# led_2835_driver_circle_34X34cm.net
KiCad netlist of a schematic drawn in Altium Designer
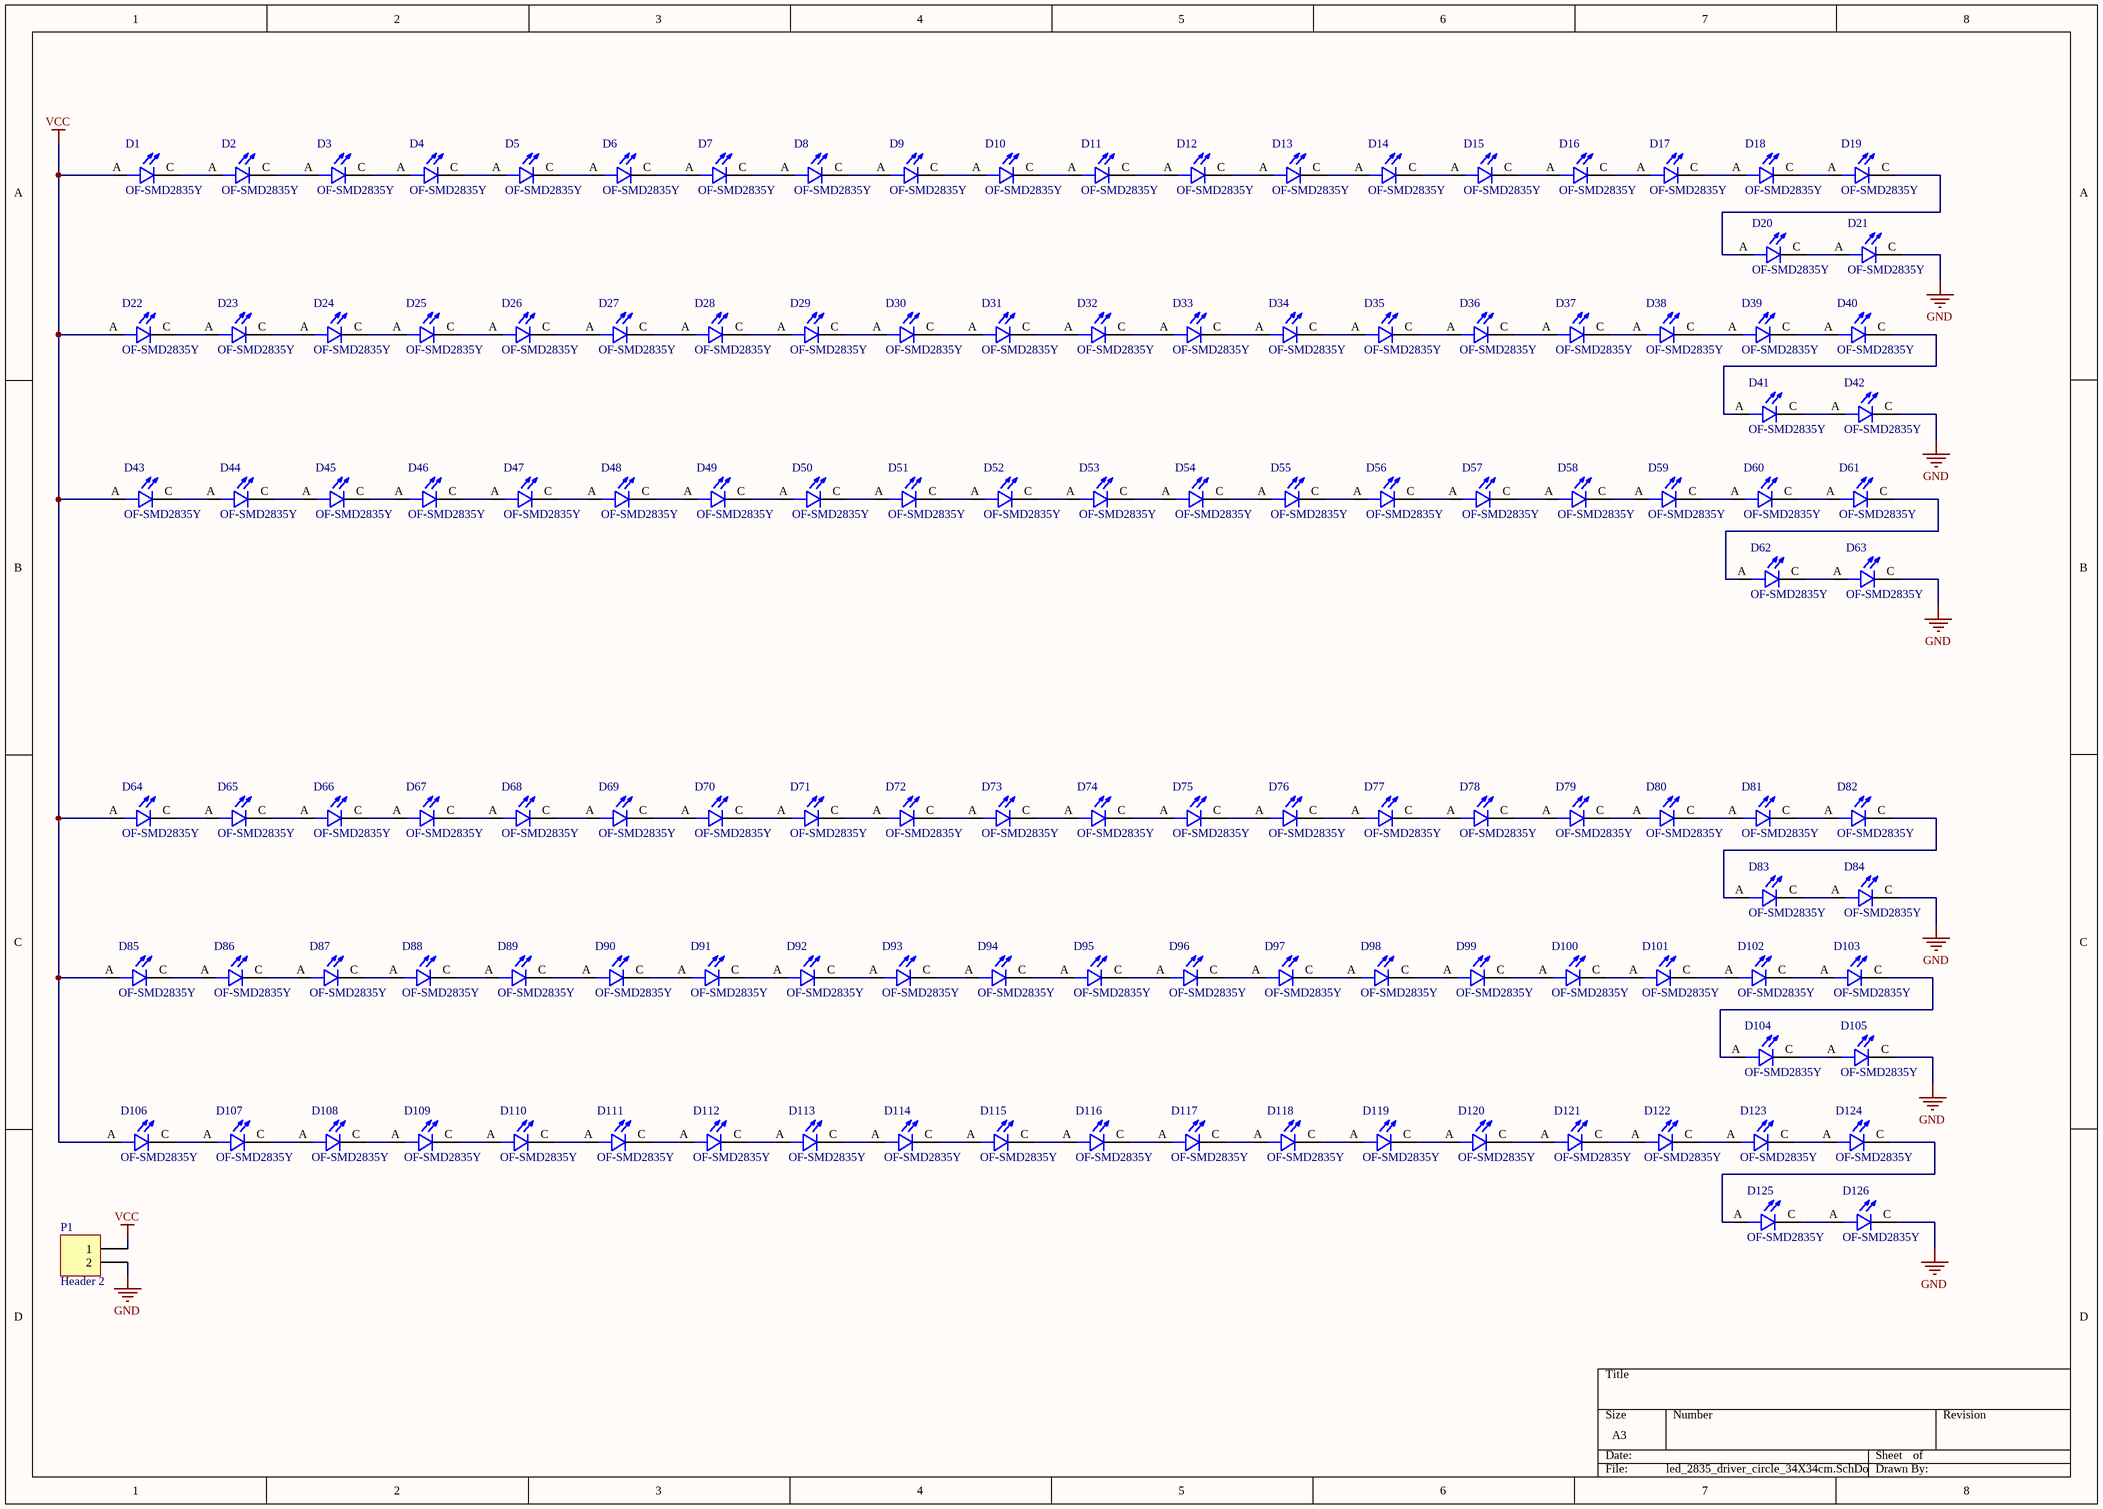
[diagram p0: led_2835_driver_circle_34X34cm.SchDoc]

(export (version "E")
  (design (tool "Eeschema 10.0.6"))
  (components
    (comp (ref "D1")
      (value "OF-SMD2835Y")
      (footprint "LED_OF-SMD2835Y")
      (description "LED; SMD; 2835, PLCC2; yellow; 2200-2800mcd; 2.8x3.5x0.75mm; 120Â°")
      (libsource (lib "OF-SMD2835Y") (part "OF-SMD2835Y"))
    )
    (comp (ref "D2")
      (value "OF-SMD2835Y")
      (footprint "LED_OF-SMD2835Y")
      (description "LED; SMD; 2835, PLCC2; yellow; 2200-2800mcd; 2.8x3.5x0.75mm; 120Â°")
      (libsource (lib "OF-SMD2835Y") (part "OF-SMD2835Y"))
    )
    (comp (ref "D3")
      (value "OF-SMD2835Y")
      (footprint "LED_OF-SMD2835Y")
      (description "LED; SMD; 2835, PLCC2; yellow; 2200-2800mcd; 2.8x3.5x0.75mm; 120Â°")
      (libsource (lib "OF-SMD2835Y") (part "OF-SMD2835Y"))
    )
    (comp (ref "D4")
      (value "OF-SMD2835Y")
      (footprint "LED_OF-SMD2835Y")
      (description "LED; SMD; 2835, PLCC2; yellow; 2200-2800mcd; 2.8x3.5x0.75mm; 120Â°")
      (libsource (lib "OF-SMD2835Y") (part "OF-SMD2835Y"))
    )
    (comp (ref "D5")
      (value "OF-SMD2835Y")
      (footprint "LED_OF-SMD2835Y")
      (description "LED; SMD; 2835, PLCC2; yellow; 2200-2800mcd; 2.8x3.5x0.75mm; 120Â°")
      (libsource (lib "OF-SMD2835Y") (part "OF-SMD2835Y"))
    )
    (comp (ref "D6")
      (value "OF-SMD2835Y")
      (footprint "LED_OF-SMD2835Y")
      (description "LED; SMD; 2835, PLCC2; yellow; 2200-2800mcd; 2.8x3.5x0.75mm; 120Â°")
      (libsource (lib "OF-SMD2835Y") (part "OF-SMD2835Y"))
    )
    (comp (ref "D7")
      (value "OF-SMD2835Y")
      (footprint "LED_OF-SMD2835Y")
      (description "LED; SMD; 2835, PLCC2; yellow; 2200-2800mcd; 2.8x3.5x0.75mm; 120Â°")
      (libsource (lib "OF-SMD2835Y") (part "OF-SMD2835Y"))
    )
    (comp (ref "D8")
      (value "OF-SMD2835Y")
      (footprint "LED_OF-SMD2835Y")
      (description "LED; SMD; 2835, PLCC2; yellow; 2200-2800mcd; 2.8x3.5x0.75mm; 120Â°")
      (libsource (lib "OF-SMD2835Y") (part "OF-SMD2835Y"))
    )
    (comp (ref "D9")
      (value "OF-SMD2835Y")
      (footprint "LED_OF-SMD2835Y")
      (description "LED; SMD; 2835, PLCC2; yellow; 2200-2800mcd; 2.8x3.5x0.75mm; 120Â°")
      (libsource (lib "OF-SMD2835Y") (part "OF-SMD2835Y"))
    )
    (comp (ref "D10")
      (value "OF-SMD2835Y")
      (footprint "LED_OF-SMD2835Y")
      (description "LED; SMD; 2835, PLCC2; yellow; 2200-2800mcd; 2.8x3.5x0.75mm; 120Â°")
      (libsource (lib "OF-SMD2835Y") (part "OF-SMD2835Y"))
    )
    (comp (ref "D11")
      (value "OF-SMD2835Y")
      (footprint "LED_OF-SMD2835Y")
      (description "LED; SMD; 2835, PLCC2; yellow; 2200-2800mcd; 2.8x3.5x0.75mm; 120Â°")
      (libsource (lib "") (part "OF-SMD2835Y_3"))
    )
    (comp (ref "D12")
      (value "OF-SMD2835Y")
      (footprint "LED_OF-SMD2835Y")
      (description "LED; SMD; 2835, PLCC2; yellow; 2200-2800mcd; 2.8x3.5x0.75mm; 120Â°")
      (libsource (lib "") (part "OF-SMD2835Y_3"))
    )
    (comp (ref "D13")
      (value "OF-SMD2835Y")
      (footprint "LED_OF-SMD2835Y")
      (description "LED; SMD; 2835, PLCC2; yellow; 2200-2800mcd; 2.8x3.5x0.75mm; 120Â°")
      (libsource (lib "") (part "OF-SMD2835Y_3"))
    )
    (comp (ref "D14")
      (value "OF-SMD2835Y")
      (footprint "LED_OF-SMD2835Y")
      (description "LED; SMD; 2835, PLCC2; yellow; 2200-2800mcd; 2.8x3.5x0.75mm; 120Â°")
      (libsource (lib "") (part "OF-SMD2835Y_3"))
    )
    (comp (ref "D15")
      (value "OF-SMD2835Y")
      (footprint "LED_OF-SMD2835Y")
      (description "LED; SMD; 2835, PLCC2; yellow; 2200-2800mcd; 2.8x3.5x0.75mm; 120Â°")
      (libsource (lib "") (part "OF-SMD2835Y_3"))
    )
    (comp (ref "D16")
      (value "OF-SMD2835Y")
      (footprint "LED_OF-SMD2835Y")
      (description "LED; SMD; 2835, PLCC2; yellow; 2200-2800mcd; 2.8x3.5x0.75mm; 120Â°")
      (libsource (lib "") (part "OF-SMD2835Y_3"))
    )
    (comp (ref "D17")
      (value "OF-SMD2835Y")
      (footprint "LED_OF-SMD2835Y")
      (description "LED; SMD; 2835, PLCC2; yellow; 2200-2800mcd; 2.8x3.5x0.75mm; 120Â°")
      (libsource (lib "") (part "OF-SMD2835Y_3"))
    )
    (comp (ref "D18")
      (value "OF-SMD2835Y")
      (footprint "LED_OF-SMD2835Y")
      (description "LED; SMD; 2835, PLCC2; yellow; 2200-2800mcd; 2.8x3.5x0.75mm; 120Â°")
      (libsource (lib "") (part "OF-SMD2835Y_3"))
    )
    (comp (ref "D19")
      (value "OF-SMD2835Y")
      (footprint "LED_OF-SMD2835Y")
      (description "LED; SMD; 2835, PLCC2; yellow; 2200-2800mcd; 2.8x3.5x0.75mm; 120Â°")
      (libsource (lib "") (part "OF-SMD2835Y_3"))
    )
    (comp (ref "D20")
      (value "OF-SMD2835Y")
      (footprint "LED_OF-SMD2835Y")
      (description "LED; SMD; 2835, PLCC2; yellow; 2200-2800mcd; 2.8x3.5x0.75mm; 120Â°")
      (libsource (lib "") (part "OF-SMD2835Y_3"))
    )
    (comp (ref "D21")
      (value "OF-SMD2835Y")
      (footprint "LED_OF-SMD2835Y")
      (description "LED; SMD; 2835, PLCC2; yellow; 2200-2800mcd; 2.8x3.5x0.75mm; 120Â°")
      (libsource (lib "") (part "OF-SMD2835Y_3"))
    )
    (comp (ref "D22")
      (value "OF-SMD2835Y")
      (footprint "LED_OF-SMD2835Y")
      (description "LED; SMD; 2835, PLCC2; yellow; 2200-2800mcd; 2.8x3.5x0.75mm; 120Â°")
      (libsource (lib "OF-SMD2835Y") (part "OF-SMD2835Y"))
    )
    (comp (ref "D23")
      (value "OF-SMD2835Y")
      (footprint "LED_OF-SMD2835Y")
      (description "LED; SMD; 2835, PLCC2; yellow; 2200-2800mcd; 2.8x3.5x0.75mm; 120Â°")
      (libsource (lib "OF-SMD2835Y") (part "OF-SMD2835Y"))
    )
    (comp (ref "D24")
      (value "OF-SMD2835Y")
      (footprint "LED_OF-SMD2835Y")
      (description "LED; SMD; 2835, PLCC2; yellow; 2200-2800mcd; 2.8x3.5x0.75mm; 120Â°")
      (libsource (lib "OF-SMD2835Y") (part "OF-SMD2835Y"))
    )
    (comp (ref "D25")
      (value "OF-SMD2835Y")
      (footprint "LED_OF-SMD2835Y")
      (description "LED; SMD; 2835, PLCC2; yellow; 2200-2800mcd; 2.8x3.5x0.75mm; 120Â°")
      (libsource (lib "OF-SMD2835Y") (part "OF-SMD2835Y"))
    )
    (comp (ref "D26")
      (value "OF-SMD2835Y")
      (footprint "LED_OF-SMD2835Y")
      (description "LED; SMD; 2835, PLCC2; yellow; 2200-2800mcd; 2.8x3.5x0.75mm; 120Â°")
      (libsource (lib "OF-SMD2835Y") (part "OF-SMD2835Y"))
    )
    (comp (ref "D27")
      (value "OF-SMD2835Y")
      (footprint "LED_OF-SMD2835Y")
      (description "LED; SMD; 2835, PLCC2; yellow; 2200-2800mcd; 2.8x3.5x0.75mm; 120Â°")
      (libsource (lib "OF-SMD2835Y") (part "OF-SMD2835Y"))
    )
    (comp (ref "D28")
      (value "OF-SMD2835Y")
      (footprint "LED_OF-SMD2835Y")
      (description "LED; SMD; 2835, PLCC2; yellow; 2200-2800mcd; 2.8x3.5x0.75mm; 120Â°")
      (libsource (lib "OF-SMD2835Y") (part "OF-SMD2835Y"))
    )
    (comp (ref "D29")
      (value "OF-SMD2835Y")
      (footprint "LED_OF-SMD2835Y")
      (description "LED; SMD; 2835, PLCC2; yellow; 2200-2800mcd; 2.8x3.5x0.75mm; 120Â°")
      (libsource (lib "OF-SMD2835Y") (part "OF-SMD2835Y"))
    )
    (comp (ref "D30")
      (value "OF-SMD2835Y")
      (footprint "LED_OF-SMD2835Y")
      (description "LED; SMD; 2835, PLCC2; yellow; 2200-2800mcd; 2.8x3.5x0.75mm; 120Â°")
      (libsource (lib "OF-SMD2835Y") (part "OF-SMD2835Y"))
    )
    (comp (ref "D31")
      (value "OF-SMD2835Y")
      (footprint "LED_OF-SMD2835Y")
      (description "LED; SMD; 2835, PLCC2; yellow; 2200-2800mcd; 2.8x3.5x0.75mm; 120Â°")
      (libsource (lib "") (part "OF-SMD2835Y_3"))
    )
    (comp (ref "D32")
      (value "OF-SMD2835Y")
      (footprint "LED_OF-SMD2835Y")
      (description "LED; SMD; 2835, PLCC2; yellow; 2200-2800mcd; 2.8x3.5x0.75mm; 120Â°")
      (libsource (lib "") (part "OF-SMD2835Y_3"))
    )
    (comp (ref "D33")
      (value "OF-SMD2835Y")
      (footprint "LED_OF-SMD2835Y")
      (description "LED; SMD; 2835, PLCC2; yellow; 2200-2800mcd; 2.8x3.5x0.75mm; 120Â°")
      (libsource (lib "") (part "OF-SMD2835Y_3"))
    )
    (comp (ref "D34")
      (value "OF-SMD2835Y")
      (footprint "LED_OF-SMD2835Y")
      (description "LED; SMD; 2835, PLCC2; yellow; 2200-2800mcd; 2.8x3.5x0.75mm; 120Â°")
      (libsource (lib "") (part "OF-SMD2835Y_3"))
    )
    (comp (ref "D35")
      (value "OF-SMD2835Y")
      (footprint "LED_OF-SMD2835Y")
      (description "LED; SMD; 2835, PLCC2; yellow; 2200-2800mcd; 2.8x3.5x0.75mm; 120Â°")
      (libsource (lib "") (part "OF-SMD2835Y_3"))
    )
    (comp (ref "D36")
      (value "OF-SMD2835Y")
      (footprint "LED_OF-SMD2835Y")
      (description "LED; SMD; 2835, PLCC2; yellow; 2200-2800mcd; 2.8x3.5x0.75mm; 120Â°")
      (libsource (lib "") (part "OF-SMD2835Y_3"))
    )
    (comp (ref "D37")
      (value "OF-SMD2835Y")
      (footprint "LED_OF-SMD2835Y")
      (description "LED; SMD; 2835, PLCC2; yellow; 2200-2800mcd; 2.8x3.5x0.75mm; 120Â°")
      (libsource (lib "") (part "OF-SMD2835Y_3"))
    )
    (comp (ref "D38")
      (value "OF-SMD2835Y")
      (footprint "LED_OF-SMD2835Y")
      (description "LED; SMD; 2835, PLCC2; yellow; 2200-2800mcd; 2.8x3.5x0.75mm; 120Â°")
      (libsource (lib "") (part "OF-SMD2835Y_3"))
    )
    (comp (ref "D39")
      (value "OF-SMD2835Y")
      (footprint "LED_OF-SMD2835Y")
      (description "LED; SMD; 2835, PLCC2; yellow; 2200-2800mcd; 2.8x3.5x0.75mm; 120Â°")
      (libsource (lib "") (part "OF-SMD2835Y_3"))
    )
    (comp (ref "D40")
      (value "OF-SMD2835Y")
      (footprint "LED_OF-SMD2835Y")
      (description "LED; SMD; 2835, PLCC2; yellow; 2200-2800mcd; 2.8x3.5x0.75mm; 120Â°")
      (libsource (lib "") (part "OF-SMD2835Y_3"))
    )
    (comp (ref "D41")
      (value "OF-SMD2835Y")
      (footprint "LED_OF-SMD2835Y")
      (description "LED; SMD; 2835, PLCC2; yellow; 2200-2800mcd; 2.8x3.5x0.75mm; 120Â°")
      (libsource (lib "") (part "OF-SMD2835Y_3"))
    )
    (comp (ref "D42")
      (value "OF-SMD2835Y")
      (footprint "LED_OF-SMD2835Y")
      (description "LED; SMD; 2835, PLCC2; yellow; 2200-2800mcd; 2.8x3.5x0.75mm; 120Â°")
      (libsource (lib "") (part "OF-SMD2835Y_3"))
    )
    (comp (ref "D43")
      (value "OF-SMD2835Y")
      (footprint "LED_OF-SMD2835Y")
      (description "LED; SMD; 2835, PLCC2; yellow; 2200-2800mcd; 2.8x3.5x0.75mm; 120Â°")
      (libsource (lib "OF-SMD2835Y") (part "OF-SMD2835Y"))
    )
    (comp (ref "D44")
      (value "OF-SMD2835Y")
      (footprint "LED_OF-SMD2835Y")
      (description "LED; SMD; 2835, PLCC2; yellow; 2200-2800mcd; 2.8x3.5x0.75mm; 120Â°")
      (libsource (lib "OF-SMD2835Y") (part "OF-SMD2835Y"))
    )
    (comp (ref "D45")
      (value "OF-SMD2835Y")
      (footprint "LED_OF-SMD2835Y")
      (description "LED; SMD; 2835, PLCC2; yellow; 2200-2800mcd; 2.8x3.5x0.75mm; 120Â°")
      (libsource (lib "OF-SMD2835Y") (part "OF-SMD2835Y"))
    )
    (comp (ref "D46")
      (value "OF-SMD2835Y")
      (footprint "LED_OF-SMD2835Y")
      (description "LED; SMD; 2835, PLCC2; yellow; 2200-2800mcd; 2.8x3.5x0.75mm; 120Â°")
      (libsource (lib "OF-SMD2835Y") (part "OF-SMD2835Y"))
    )
    (comp (ref "D47")
      (value "OF-SMD2835Y")
      (footprint "LED_OF-SMD2835Y")
      (description "LED; SMD; 2835, PLCC2; yellow; 2200-2800mcd; 2.8x3.5x0.75mm; 120Â°")
      (libsource (lib "OF-SMD2835Y") (part "OF-SMD2835Y"))
    )
    (comp (ref "D48")
      (value "OF-SMD2835Y")
      (footprint "LED_OF-SMD2835Y")
      (description "LED; SMD; 2835, PLCC2; yellow; 2200-2800mcd; 2.8x3.5x0.75mm; 120Â°")
      (libsource (lib "OF-SMD2835Y") (part "OF-SMD2835Y"))
    )
    (comp (ref "D49")
      (value "OF-SMD2835Y")
      (footprint "LED_OF-SMD2835Y")
      (description "LED; SMD; 2835, PLCC2; yellow; 2200-2800mcd; 2.8x3.5x0.75mm; 120Â°")
      (libsource (lib "OF-SMD2835Y") (part "OF-SMD2835Y"))
    )
    (comp (ref "D50")
      (value "OF-SMD2835Y")
      (footprint "LED_OF-SMD2835Y")
      (description "LED; SMD; 2835, PLCC2; yellow; 2200-2800mcd; 2.8x3.5x0.75mm; 120Â°")
      (libsource (lib "OF-SMD2835Y") (part "OF-SMD2835Y"))
    )
    (comp (ref "D51")
      (value "OF-SMD2835Y")
      (footprint "LED_OF-SMD2835Y")
      (description "LED; SMD; 2835, PLCC2; yellow; 2200-2800mcd; 2.8x3.5x0.75mm; 120Â°")
      (libsource (lib "OF-SMD2835Y") (part "OF-SMD2835Y"))
    )
    (comp (ref "D52")
      (value "OF-SMD2835Y")
      (footprint "LED_OF-SMD2835Y")
      (description "LED; SMD; 2835, PLCC2; yellow; 2200-2800mcd; 2.8x3.5x0.75mm; 120Â°")
      (libsource (lib "OF-SMD2835Y") (part "OF-SMD2835Y"))
    )
    (comp (ref "D53")
      (value "OF-SMD2835Y")
      (footprint "LED_OF-SMD2835Y")
      (description "LED; SMD; 2835, PLCC2; yellow; 2200-2800mcd; 2.8x3.5x0.75mm; 120Â°")
      (libsource (lib "") (part "OF-SMD2835Y_3"))
    )
    (comp (ref "D54")
      (value "OF-SMD2835Y")
      (footprint "LED_OF-SMD2835Y")
      (description "LED; SMD; 2835, PLCC2; yellow; 2200-2800mcd; 2.8x3.5x0.75mm; 120Â°")
      (libsource (lib "") (part "OF-SMD2835Y_3"))
    )
    (comp (ref "D55")
      (value "OF-SMD2835Y")
      (footprint "LED_OF-SMD2835Y")
      (description "LED; SMD; 2835, PLCC2; yellow; 2200-2800mcd; 2.8x3.5x0.75mm; 120Â°")
      (libsource (lib "") (part "OF-SMD2835Y_3"))
    )
    (comp (ref "D56")
      (value "OF-SMD2835Y")
      (footprint "LED_OF-SMD2835Y")
      (description "LED; SMD; 2835, PLCC2; yellow; 2200-2800mcd; 2.8x3.5x0.75mm; 120Â°")
      (libsource (lib "") (part "OF-SMD2835Y_3"))
    )
    (comp (ref "D57")
      (value "OF-SMD2835Y")
      (footprint "LED_OF-SMD2835Y")
      (description "LED; SMD; 2835, PLCC2; yellow; 2200-2800mcd; 2.8x3.5x0.75mm; 120Â°")
      (libsource (lib "") (part "OF-SMD2835Y_3"))
    )
    (comp (ref "D58")
      (value "OF-SMD2835Y")
      (footprint "LED_OF-SMD2835Y")
      (description "LED; SMD; 2835, PLCC2; yellow; 2200-2800mcd; 2.8x3.5x0.75mm; 120Â°")
      (libsource (lib "") (part "OF-SMD2835Y_3"))
    )
    (comp (ref "D59")
      (value "OF-SMD2835Y")
      (footprint "LED_OF-SMD2835Y")
      (description "LED; SMD; 2835, PLCC2; yellow; 2200-2800mcd; 2.8x3.5x0.75mm; 120Â°")
      (libsource (lib "") (part "OF-SMD2835Y_3"))
    )
    (comp (ref "D60")
      (value "OF-SMD2835Y")
      (footprint "LED_OF-SMD2835Y")
      (description "LED; SMD; 2835, PLCC2; yellow; 2200-2800mcd; 2.8x3.5x0.75mm; 120Â°")
      (libsource (lib "") (part "OF-SMD2835Y_3"))
    )
    (comp (ref "D61")
      (value "OF-SMD2835Y")
      (footprint "LED_OF-SMD2835Y")
      (description "LED; SMD; 2835, PLCC2; yellow; 2200-2800mcd; 2.8x3.5x0.75mm; 120Â°")
      (libsource (lib "") (part "OF-SMD2835Y_3"))
    )
    (comp (ref "D62")
      (value "OF-SMD2835Y")
      (footprint "LED_OF-SMD2835Y")
      (description "LED; SMD; 2835, PLCC2; yellow; 2200-2800mcd; 2.8x3.5x0.75mm; 120Â°")
      (libsource (lib "") (part "OF-SMD2835Y_1"))
    )
    (comp (ref "D63")
      (value "OF-SMD2835Y")
      (footprint "LED_OF-SMD2835Y")
      (description "LED; SMD; 2835, PLCC2; yellow; 2200-2800mcd; 2.8x3.5x0.75mm; 120Â°")
      (libsource (lib "") (part "OF-SMD2835Y_1"))
    )
    (comp (ref "D64")
      (value "OF-SMD2835Y")
      (footprint "LED_OF-SMD2835Y")
      (description "LED; SMD; 2835, PLCC2; yellow; 2200-2800mcd; 2.8x3.5x0.75mm; 120Â°")
      (libsource (lib "") (part "OF-SMD2835Y_2"))
    )
    (comp (ref "D65")
      (value "OF-SMD2835Y")
      (footprint "LED_OF-SMD2835Y")
      (description "LED; SMD; 2835, PLCC2; yellow; 2200-2800mcd; 2.8x3.5x0.75mm; 120Â°")
      (libsource (lib "") (part "OF-SMD2835Y_2"))
    )
    (comp (ref "D66")
      (value "OF-SMD2835Y")
      (footprint "LED_OF-SMD2835Y")
      (description "LED; SMD; 2835, PLCC2; yellow; 2200-2800mcd; 2.8x3.5x0.75mm; 120Â°")
      (libsource (lib "") (part "OF-SMD2835Y_2"))
    )
    (comp (ref "D67")
      (value "OF-SMD2835Y")
      (footprint "LED_OF-SMD2835Y")
      (description "LED; SMD; 2835, PLCC2; yellow; 2200-2800mcd; 2.8x3.5x0.75mm; 120Â°")
      (libsource (lib "") (part "OF-SMD2835Y_2"))
    )
    (comp (ref "D68")
      (value "OF-SMD2835Y")
      (footprint "LED_OF-SMD2835Y")
      (description "LED; SMD; 2835, PLCC2; yellow; 2200-2800mcd; 2.8x3.5x0.75mm; 120Â°")
      (libsource (lib "") (part "OF-SMD2835Y_2"))
    )
    (comp (ref "D69")
      (value "OF-SMD2835Y")
      (footprint "LED_OF-SMD2835Y")
      (description "LED; SMD; 2835, PLCC2; yellow; 2200-2800mcd; 2.8x3.5x0.75mm; 120Â°")
      (libsource (lib "") (part "OF-SMD2835Y_2"))
    )
    (comp (ref "D70")
      (value "OF-SMD2835Y")
      (footprint "LED_OF-SMD2835Y")
      (description "LED; SMD; 2835, PLCC2; yellow; 2200-2800mcd; 2.8x3.5x0.75mm; 120Â°")
      (libsource (lib "") (part "OF-SMD2835Y_2"))
    )
    (comp (ref "D71")
      (value "OF-SMD2835Y")
      (footprint "LED_OF-SMD2835Y")
      (description "LED; SMD; 2835, PLCC2; yellow; 2200-2800mcd; 2.8x3.5x0.75mm; 120Â°")
      (libsource (lib "") (part "OF-SMD2835Y_2"))
    )
    (comp (ref "D72")
      (value "OF-SMD2835Y")
      (footprint "LED_OF-SMD2835Y")
      (description "LED; SMD; 2835, PLCC2; yellow; 2200-2800mcd; 2.8x3.5x0.75mm; 120Â°")
      (libsource (lib "") (part "OF-SMD2835Y_2"))
    )
    (comp (ref "D73")
      (value "OF-SMD2835Y")
      (footprint "LED_OF-SMD2835Y")
      (description "LED; SMD; 2835, PLCC2; yellow; 2200-2800mcd; 2.8x3.5x0.75mm; 120Â°")
      (libsource (lib "") (part "OF-SMD2835Y_1"))
    )
    (comp (ref "D74")
      (value "OF-SMD2835Y")
      (footprint "LED_OF-SMD2835Y")
      (description "LED; SMD; 2835, PLCC2; yellow; 2200-2800mcd; 2.8x3.5x0.75mm; 120Â°")
      (libsource (lib "") (part "OF-SMD2835Y_1"))
    )
    (comp (ref "D75")
      (value "OF-SMD2835Y")
      (footprint "LED_OF-SMD2835Y")
      (description "LED; SMD; 2835, PLCC2; yellow; 2200-2800mcd; 2.8x3.5x0.75mm; 120Â°")
      (libsource (lib "") (part "OF-SMD2835Y_1"))
    )
    (comp (ref "D76")
      (value "OF-SMD2835Y")
      (footprint "LED_OF-SMD2835Y")
      (description "LED; SMD; 2835, PLCC2; yellow; 2200-2800mcd; 2.8x3.5x0.75mm; 120Â°")
      (libsource (lib "") (part "OF-SMD2835Y_1"))
    )
    (comp (ref "D77")
      (value "OF-SMD2835Y")
      (footprint "LED_OF-SMD2835Y")
      (description "LED; SMD; 2835, PLCC2; yellow; 2200-2800mcd; 2.8x3.5x0.75mm; 120Â°")
      (libsource (lib "") (part "OF-SMD2835Y_1"))
    )
    (comp (ref "D78")
      (value "OF-SMD2835Y")
      (footprint "LED_OF-SMD2835Y")
      (description "LED; SMD; 2835, PLCC2; yellow; 2200-2800mcd; 2.8x3.5x0.75mm; 120Â°")
      (libsource (lib "") (part "OF-SMD2835Y_1"))
    )
    (comp (ref "D79")
      (value "OF-SMD2835Y")
      (footprint "LED_OF-SMD2835Y")
      (description "LED; SMD; 2835, PLCC2; yellow; 2200-2800mcd; 2.8x3.5x0.75mm; 120Â°")
      (libsource (lib "") (part "OF-SMD2835Y_1"))
    )
    (comp (ref "D80")
      (value "OF-SMD2835Y")
      (footprint "LED_OF-SMD2835Y")
      (description "LED; SMD; 2835, PLCC2; yellow; 2200-2800mcd; 2.8x3.5x0.75mm; 120Â°")
      (libsource (lib "") (part "OF-SMD2835Y_1"))
    )
    (comp (ref "D81")
      (value "OF-SMD2835Y")
      (footprint "LED_OF-SMD2835Y")
      (description "LED; SMD; 2835, PLCC2; yellow; 2200-2800mcd; 2.8x3.5x0.75mm; 120Â°")
      (libsource (lib "") (part "OF-SMD2835Y_1"))
    )
    (comp (ref "D82")
      (value "OF-SMD2835Y")
      (footprint "LED_OF-SMD2835Y")
      (description "LED; SMD; 2835, PLCC2; yellow; 2200-2800mcd; 2.8x3.5x0.75mm; 120Â°")
      (libsource (lib "") (part "OF-SMD2835Y_1"))
    )
    (comp (ref "D83")
      (value "OF-SMD2835Y")
      (footprint "LED_OF-SMD2835Y")
      (description "LED; SMD; 2835, PLCC2; yellow; 2200-2800mcd; 2.8x3.5x0.75mm; 120Â°")
      (libsource (lib "") (part "OF-SMD2835Y_1"))
    )
    (comp (ref "D84")
      (value "OF-SMD2835Y")
      (footprint "LED_OF-SMD2835Y")
      (description "LED; SMD; 2835, PLCC2; yellow; 2200-2800mcd; 2.8x3.5x0.75mm; 120Â°")
      (libsource (lib "") (part "OF-SMD2835Y_1"))
    )
    (comp (ref "D85")
      (value "OF-SMD2835Y")
      (footprint "LED_OF-SMD2835Y")
      (description "LED; SMD; 2835, PLCC2; yellow; 2200-2800mcd; 2.8x3.5x0.75mm; 120Â°")
      (libsource (lib "") (part "OF-SMD2835Y_2"))
    )
    (comp (ref "D86")
      (value "OF-SMD2835Y")
      (footprint "LED_OF-SMD2835Y")
      (description "LED; SMD; 2835, PLCC2; yellow; 2200-2800mcd; 2.8x3.5x0.75mm; 120Â°")
      (libsource (lib "") (part "OF-SMD2835Y_2"))
    )
    (comp (ref "D87")
      (value "OF-SMD2835Y")
      (footprint "LED_OF-SMD2835Y")
      (description "LED; SMD; 2835, PLCC2; yellow; 2200-2800mcd; 2.8x3.5x0.75mm; 120Â°")
      (libsource (lib "") (part "OF-SMD2835Y_2"))
    )
    (comp (ref "D88")
      (value "OF-SMD2835Y")
      (footprint "LED_OF-SMD2835Y")
      (description "LED; SMD; 2835, PLCC2; yellow; 2200-2800mcd; 2.8x3.5x0.75mm; 120Â°")
      (libsource (lib "") (part "OF-SMD2835Y_2"))
    )
    (comp (ref "D89")
      (value "OF-SMD2835Y")
      (footprint "LED_OF-SMD2835Y")
      (description "LED; SMD; 2835, PLCC2; yellow; 2200-2800mcd; 2.8x3.5x0.75mm; 120Â°")
      (libsource (lib "") (part "OF-SMD2835Y_2"))
    )
    (comp (ref "D90")
      (value "OF-SMD2835Y")
      (footprint "LED_OF-SMD2835Y")
      (description "LED; SMD; 2835, PLCC2; yellow; 2200-2800mcd; 2.8x3.5x0.75mm; 120Â°")
      (libsource (lib "") (part "OF-SMD2835Y_2"))
    )
    (comp (ref "D91")
      (value "OF-SMD2835Y")
      (footprint "LED_OF-SMD2835Y")
      (description "LED; SMD; 2835, PLCC2; yellow; 2200-2800mcd; 2.8x3.5x0.75mm; 120Â°")
      (libsource (lib "") (part "OF-SMD2835Y_2"))
    )
    (comp (ref "D92")
      (value "OF-SMD2835Y")
      (footprint "LED_OF-SMD2835Y")
      (description "LED; SMD; 2835, PLCC2; yellow; 2200-2800mcd; 2.8x3.5x0.75mm; 120Â°")
      (libsource (lib "") (part "OF-SMD2835Y_2"))
    )
    (comp (ref "D93")
      (value "OF-SMD2835Y")
      (footprint "LED_OF-SMD2835Y")
      (description "LED; SMD; 2835, PLCC2; yellow; 2200-2800mcd; 2.8x3.5x0.75mm; 120Â°")
      (libsource (lib "") (part "OF-SMD2835Y_1"))
    )
    (comp (ref "D94")
      (value "OF-SMD2835Y")
      (footprint "LED_OF-SMD2835Y")
      (description "LED; SMD; 2835, PLCC2; yellow; 2200-2800mcd; 2.8x3.5x0.75mm; 120Â°")
      (libsource (lib "") (part "OF-SMD2835Y_1"))
    )
    (comp (ref "D95")
      (value "OF-SMD2835Y")
      (footprint "LED_OF-SMD2835Y")
      (description "LED; SMD; 2835, PLCC2; yellow; 2200-2800mcd; 2.8x3.5x0.75mm; 120Â°")
      (libsource (lib "") (part "OF-SMD2835Y_1"))
    )
    (comp (ref "D96")
      (value "OF-SMD2835Y")
      (footprint "LED_OF-SMD2835Y")
      (description "LED; SMD; 2835, PLCC2; yellow; 2200-2800mcd; 2.8x3.5x0.75mm; 120Â°")
      (libsource (lib "") (part "OF-SMD2835Y_1"))
    )
    (comp (ref "D97")
      (value "OF-SMD2835Y")
      (footprint "LED_OF-SMD2835Y")
      (description "LED; SMD; 2835, PLCC2; yellow; 2200-2800mcd; 2.8x3.5x0.75mm; 120Â°")
      (libsource (lib "") (part "OF-SMD2835Y_1"))
    )
    (comp (ref "D98")
      (value "OF-SMD2835Y")
      (footprint "LED_OF-SMD2835Y")
      (description "LED; SMD; 2835, PLCC2; yellow; 2200-2800mcd; 2.8x3.5x0.75mm; 120Â°")
      (libsource (lib "") (part "OF-SMD2835Y_1"))
    )
    (comp (ref "D99")
      (value "OF-SMD2835Y")
      (footprint "LED_OF-SMD2835Y")
      (description "LED; SMD; 2835, PLCC2; yellow; 2200-2800mcd; 2.8x3.5x0.75mm; 120Â°")
      (libsource (lib "") (part "OF-SMD2835Y_1"))
    )
    (comp (ref "D100")
      (value "OF-SMD2835Y")
      (footprint "LED_OF-SMD2835Y")
      (description "LED; SMD; 2835, PLCC2; yellow; 2200-2800mcd; 2.8x3.5x0.75mm; 120Â°")
      (libsource (lib "") (part "OF-SMD2835Y_1"))
    )
    (comp (ref "D101")
      (value "OF-SMD2835Y")
      (footprint "LED_OF-SMD2835Y")
      (description "LED; SMD; 2835, PLCC2; yellow; 2200-2800mcd; 2.8x3.5x0.75mm; 120Â°")
      (libsource (lib "") (part "OF-SMD2835Y_1"))
    )
    (comp (ref "D102")
      (value "OF-SMD2835Y")
      (footprint "LED_OF-SMD2835Y")
      (description "LED; SMD; 2835, PLCC2; yellow; 2200-2800mcd; 2.8x3.5x0.75mm; 120Â°")
      (libsource (lib "") (part "OF-SMD2835Y_1"))
    )
    (comp (ref "D103")
      (value "OF-SMD2835Y")
      (footprint "LED_OF-SMD2835Y")
      (description "LED; SMD; 2835, PLCC2; yellow; 2200-2800mcd; 2.8x3.5x0.75mm; 120Â°")
      (libsource (lib "") (part "OF-SMD2835Y_1"))
    )
    (comp (ref "D104")
      (value "OF-SMD2835Y")
      (footprint "LED_OF-SMD2835Y")
      (description "LED; SMD; 2835, PLCC2; yellow; 2200-2800mcd; 2.8x3.5x0.75mm; 120Â°")
      (libsource (lib "") (part "OF-SMD2835Y_1"))
    )
    (comp (ref "D105")
      (value "OF-SMD2835Y")
      (footprint "LED_OF-SMD2835Y")
      (description "LED; SMD; 2835, PLCC2; yellow; 2200-2800mcd; 2.8x3.5x0.75mm; 120Â°")
      (libsource (lib "") (part "OF-SMD2835Y_1"))
    )
    (comp (ref "D106")
      (value "OF-SMD2835Y")
      (footprint "LED_OF-SMD2835Y")
      (description "LED; SMD; 2835, PLCC2; yellow; 2200-2800mcd; 2.8x3.5x0.75mm; 120Â°")
      (libsource (lib "") (part "OF-SMD2835Y_2"))
    )
    (comp (ref "D107")
      (value "OF-SMD2835Y")
      (footprint "LED_OF-SMD2835Y")
      (description "LED; SMD; 2835, PLCC2; yellow; 2200-2800mcd; 2.8x3.5x0.75mm; 120Â°")
      (libsource (lib "") (part "OF-SMD2835Y_2"))
    )
    (comp (ref "D108")
      (value "OF-SMD2835Y")
      (footprint "LED_OF-SMD2835Y")
      (description "LED; SMD; 2835, PLCC2; yellow; 2200-2800mcd; 2.8x3.5x0.75mm; 120Â°")
      (libsource (lib "") (part "OF-SMD2835Y_2"))
    )
    (comp (ref "D109")
      (value "OF-SMD2835Y")
      (footprint "LED_OF-SMD2835Y")
      (description "LED; SMD; 2835, PLCC2; yellow; 2200-2800mcd; 2.8x3.5x0.75mm; 120Â°")
      (libsource (lib "") (part "OF-SMD2835Y_2"))
    )
    (comp (ref "D110")
      (value "OF-SMD2835Y")
      (footprint "LED_OF-SMD2835Y")
      (description "LED; SMD; 2835, PLCC2; yellow; 2200-2800mcd; 2.8x3.5x0.75mm; 120Â°")
      (libsource (lib "") (part "OF-SMD2835Y_2"))
    )
    (comp (ref "D111")
      (value "OF-SMD2835Y")
      (footprint "LED_OF-SMD2835Y")
      (description "LED; SMD; 2835, PLCC2; yellow; 2200-2800mcd; 2.8x3.5x0.75mm; 120Â°")
      (libsource (lib "") (part "OF-SMD2835Y_2"))
    )
    (comp (ref "D112")
      (value "OF-SMD2835Y")
      (footprint "LED_OF-SMD2835Y")
      (description "LED; SMD; 2835, PLCC2; yellow; 2200-2800mcd; 2.8x3.5x0.75mm; 120Â°")
      (libsource (lib "") (part "OF-SMD2835Y_2"))
    )
    (comp (ref "D113")
      (value "OF-SMD2835Y")
      (footprint "LED_OF-SMD2835Y")
      (description "LED; SMD; 2835, PLCC2; yellow; 2200-2800mcd; 2.8x3.5x0.75mm; 120Â°")
      (libsource (lib "") (part "OF-SMD2835Y_2"))
    )
    (comp (ref "D114")
      (value "OF-SMD2835Y")
      (footprint "LED_OF-SMD2835Y")
      (description "LED; SMD; 2835, PLCC2; yellow; 2200-2800mcd; 2.8x3.5x0.75mm; 120Â°")
      (libsource (lib "") (part "OF-SMD2835Y_2"))
    )
    (comp (ref "D115")
      (value "OF-SMD2835Y")
      (footprint "LED_OF-SMD2835Y")
      (description "LED; SMD; 2835, PLCC2; yellow; 2200-2800mcd; 2.8x3.5x0.75mm; 120Â°")
      (libsource (lib "") (part "OF-SMD2835Y_2"))
    )
    (comp (ref "D116")
      (value "OF-SMD2835Y")
      (footprint "LED_OF-SMD2835Y")
      (description "LED; SMD; 2835, PLCC2; yellow; 2200-2800mcd; 2.8x3.5x0.75mm; 120Â°")
      (libsource (lib "") (part "OF-SMD2835Y_1"))
    )
    (comp (ref "D117")
      (value "OF-SMD2835Y")
      (footprint "LED_OF-SMD2835Y")
      (description "LED; SMD; 2835, PLCC2; yellow; 2200-2800mcd; 2.8x3.5x0.75mm; 120Â°")
      (libsource (lib "") (part "OF-SMD2835Y_1"))
    )
    (comp (ref "D118")
      (value "OF-SMD2835Y")
      (footprint "LED_OF-SMD2835Y")
      (description "LED; SMD; 2835, PLCC2; yellow; 2200-2800mcd; 2.8x3.5x0.75mm; 120Â°")
      (libsource (lib "") (part "OF-SMD2835Y_1"))
    )
    (comp (ref "D119")
      (value "OF-SMD2835Y")
      (footprint "LED_OF-SMD2835Y")
      (description "LED; SMD; 2835, PLCC2; yellow; 2200-2800mcd; 2.8x3.5x0.75mm; 120Â°")
      (libsource (lib "") (part "OF-SMD2835Y_1"))
    )
    (comp (ref "D120")
      (value "OF-SMD2835Y")
      (footprint "LED_OF-SMD2835Y")
      (description "LED; SMD; 2835, PLCC2; yellow; 2200-2800mcd; 2.8x3.5x0.75mm; 120Â°")
      (libsource (lib "") (part "OF-SMD2835Y_1"))
    )
    (comp (ref "D121")
      (value "OF-SMD2835Y")
      (footprint "LED_OF-SMD2835Y")
      (description "LED; SMD; 2835, PLCC2; yellow; 2200-2800mcd; 2.8x3.5x0.75mm; 120Â°")
      (libsource (lib "") (part "OF-SMD2835Y_1"))
    )
    (comp (ref "D122")
      (value "OF-SMD2835Y")
      (footprint "LED_OF-SMD2835Y")
      (description "LED; SMD; 2835, PLCC2; yellow; 2200-2800mcd; 2.8x3.5x0.75mm; 120Â°")
      (libsource (lib "") (part "OF-SMD2835Y_1"))
    )
    (comp (ref "D123")
      (value "OF-SMD2835Y")
      (footprint "LED_OF-SMD2835Y")
      (description "LED; SMD; 2835, PLCC2; yellow; 2200-2800mcd; 2.8x3.5x0.75mm; 120Â°")
      (libsource (lib "") (part "OF-SMD2835Y_1"))
    )
    (comp (ref "D124")
      (value "OF-SMD2835Y")
      (footprint "LED_OF-SMD2835Y")
      (description "LED; SMD; 2835, PLCC2; yellow; 2200-2800mcd; 2.8x3.5x0.75mm; 120Â°")
      (libsource (lib "") (part "OF-SMD2835Y_1"))
    )
    (comp (ref "D125")
      (value "OF-SMD2835Y")
      (footprint "LED_OF-SMD2835Y")
      (description "LED; SMD; 2835, PLCC2; yellow; 2200-2800mcd; 2.8x3.5x0.75mm; 120Â°")
      (libsource (lib "") (part "OF-SMD2835Y_1"))
    )
    (comp (ref "D126")
      (value "OF-SMD2835Y")
      (footprint "LED_OF-SMD2835Y")
      (description "LED; SMD; 2835, PLCC2; yellow; 2200-2800mcd; 2.8x3.5x0.75mm; 120Â°")
      (libsource (lib "") (part "OF-SMD2835Y_1"))
    )
    (comp (ref "P1")
      (value "Header 2")
      (footprint "HDR1X2_SMD")
      (description "Header, 2-Pin")
      (fields (field (name "PUBLISHER") "Altium Limited"))
      (libsource (lib "Miscellaneous Connectors") (part "Header 2"))
    )
  )
  (nets
    (net (code "1") (name "GND") (class "Default")
      (node (ref "D105") (pin "C") (pinfunction "C_C") (pintype "passive"))
      (node (ref "D126") (pin "C") (pinfunction "C_C") (pintype "passive"))
      (node (ref "D21") (pin "C") (pinfunction "C_C") (pintype "passive"))
      (node (ref "D42") (pin "C") (pinfunction "C_C") (pintype "passive"))
      (node (ref "D63") (pin "C") (pinfunction "C_C") (pintype "passive"))
      (node (ref "D84") (pin "C") (pinfunction "C_C") (pintype "passive"))
      (node (ref "P1") (pin "GND") (pinfunction "2_GND") (pintype "passive"))
    )
    (net (code "2") (name "Net-(D1-PadC)") (class "Default")
      (node (ref "D1") (pin "C") (pinfunction "C_C") (pintype "passive"))
      (node (ref "D2") (pin "A") (pinfunction "A_A") (pintype "passive"))
    )
    (net (code "3") (name "Net-(D2-PadC)") (class "Default")
      (node (ref "D2") (pin "C") (pinfunction "C_C") (pintype "passive"))
      (node (ref "D3") (pin "A") (pinfunction "A_A") (pintype "passive"))
    )
    (net (code "4") (name "Net-(D3-PadC)") (class "Default")
      (node (ref "D3") (pin "C") (pinfunction "C_C") (pintype "passive"))
      (node (ref "D4") (pin "A") (pinfunction "A_A") (pintype "passive"))
    )
    (net (code "5") (name "Net-(D4-PadC)") (class "Default")
      (node (ref "D4") (pin "C") (pinfunction "C_C") (pintype "passive"))
      (node (ref "D5") (pin "A") (pinfunction "A_A") (pintype "passive"))
    )
    (net (code "6") (name "Net-(D5-PadC)") (class "Default")
      (node (ref "D5") (pin "C") (pinfunction "C_C") (pintype "passive"))
      (node (ref "D6") (pin "A") (pinfunction "A_A") (pintype "passive"))
    )
    (net (code "7") (name "Net-(D6-PadC)") (class "Default")
      (node (ref "D6") (pin "C") (pinfunction "C_C") (pintype "passive"))
      (node (ref "D7") (pin "A") (pinfunction "A_A") (pintype "passive"))
    )
    (net (code "8") (name "Net-(D7-PadC)") (class "Default")
      (node (ref "D7") (pin "C") (pinfunction "C_C") (pintype "passive"))
      (node (ref "D8") (pin "A") (pinfunction "A_A") (pintype "passive"))
    )
    (net (code "9") (name "Net-(D8-PadC)") (class "Default")
      (node (ref "D8") (pin "C") (pinfunction "C_C") (pintype "passive"))
      (node (ref "D9") (pin "A") (pinfunction "A_A") (pintype "passive"))
    )
    (net (code "10") (name "Net-(D10-PadA)") (class "Default")
      (node (ref "D10") (pin "A") (pinfunction "A_A") (pintype "passive"))
      (node (ref "D9") (pin "C") (pinfunction "C_C") (pintype "passive"))
    )
    (net (code "11") (name "Net-(D10-PadC)") (class "Default")
      (node (ref "D10") (pin "C") (pinfunction "C_C") (pintype "passive"))
      (node (ref "D11") (pin "A") (pinfunction "A_A") (pintype "passive"))
    )
    (net (code "12") (name "Net-(D11-PadC)") (class "Default")
      (node (ref "D11") (pin "C") (pinfunction "C_C") (pintype "passive"))
      (node (ref "D12") (pin "A") (pinfunction "A_A") (pintype "passive"))
    )
    (net (code "13") (name "Net-(D12-PadC)") (class "Default")
      (node (ref "D12") (pin "C") (pinfunction "C_C") (pintype "passive"))
      (node (ref "D13") (pin "A") (pinfunction "A_A") (pintype "passive"))
    )
    (net (code "14") (name "Net-(D13-PadC)") (class "Default")
      (node (ref "D13") (pin "C") (pinfunction "C_C") (pintype "passive"))
      (node (ref "D14") (pin "A") (pinfunction "A_A") (pintype "passive"))
    )
    (net (code "15") (name "Net-(D14-PadC)") (class "Default")
      (node (ref "D14") (pin "C") (pinfunction "C_C") (pintype "passive"))
      (node (ref "D15") (pin "A") (pinfunction "A_A") (pintype "passive"))
    )
    (net (code "16") (name "Net-(D15-PadC)") (class "Default")
      (node (ref "D15") (pin "C") (pinfunction "C_C") (pintype "passive"))
      (node (ref "D16") (pin "A") (pinfunction "A_A") (pintype "passive"))
    )
    (net (code "17") (name "Net-(D16-PadC)") (class "Default")
      (node (ref "D16") (pin "C") (pinfunction "C_C") (pintype "passive"))
      (node (ref "D17") (pin "A") (pinfunction "A_A") (pintype "passive"))
    )
    (net (code "18") (name "Net-(D17-PadC)") (class "Default")
      (node (ref "D17") (pin "C") (pinfunction "C_C") (pintype "passive"))
      (node (ref "D18") (pin "A") (pinfunction "A_A") (pintype "passive"))
    )
    (net (code "19") (name "Net-(D18-PadC)") (class "Default")
      (node (ref "D18") (pin "C") (pinfunction "C_C") (pintype "passive"))
      (node (ref "D19") (pin "A") (pinfunction "A_A") (pintype "passive"))
    )
    (net (code "20") (name "Net-(D19-PadC)") (class "Default")
      (node (ref "D19") (pin "C") (pinfunction "C_C") (pintype "passive"))
      (node (ref "D20") (pin "A") (pinfunction "A_A") (pintype "passive"))
    )
    (net (code "21") (name "Net-(D20-PadC)") (class "Default")
      (node (ref "D20") (pin "C") (pinfunction "C_C") (pintype "passive"))
      (node (ref "D21") (pin "A") (pinfunction "A_A") (pintype "passive"))
    )
    (net (code "22") (name "Net-(D22-PadC)") (class "Default")
      (node (ref "D22") (pin "C") (pinfunction "C_C") (pintype "passive"))
      (node (ref "D23") (pin "A") (pinfunction "A_A") (pintype "passive"))
    )
    (net (code "23") (name "Net-(D23-PadC)") (class "Default")
      (node (ref "D23") (pin "C") (pinfunction "C_C") (pintype "passive"))
      (node (ref "D24") (pin "A") (pinfunction "A_A") (pintype "passive"))
    )
    (net (code "24") (name "Net-(D24-PadC)") (class "Default")
      (node (ref "D24") (pin "C") (pinfunction "C_C") (pintype "passive"))
      (node (ref "D25") (pin "A") (pinfunction "A_A") (pintype "passive"))
    )
    (net (code "25") (name "Net-(D25-PadC)") (class "Default")
      (node (ref "D25") (pin "C") (pinfunction "C_C") (pintype "passive"))
      (node (ref "D26") (pin "A") (pinfunction "A_A") (pintype "passive"))
    )
    (net (code "26") (name "Net-(D26-PadC)") (class "Default")
      (node (ref "D26") (pin "C") (pinfunction "C_C") (pintype "passive"))
      (node (ref "D27") (pin "A") (pinfunction "A_A") (pintype "passive"))
    )
    (net (code "27") (name "Net-(D27-PadC)") (class "Default")
      (node (ref "D27") (pin "C") (pinfunction "C_C") (pintype "passive"))
      (node (ref "D28") (pin "A") (pinfunction "A_A") (pintype "passive"))
    )
    (net (code "28") (name "Net-(D28-PadC)") (class "Default")
      (node (ref "D28") (pin "C") (pinfunction "C_C") (pintype "passive"))
      (node (ref "D29") (pin "A") (pinfunction "A_A") (pintype "passive"))
    )
    (net (code "29") (name "Net-(D29-PadC)") (class "Default")
      (node (ref "D29") (pin "C") (pinfunction "C_C") (pintype "passive"))
      (node (ref "D30") (pin "A") (pinfunction "A_A") (pintype "passive"))
    )
    (net (code "30") (name "Net-(D30-PadC)") (class "Default")
      (node (ref "D30") (pin "C") (pinfunction "C_C") (pintype "passive"))
      (node (ref "D31") (pin "A") (pinfunction "A_A") (pintype "passive"))
    )
    (net (code "31") (name "Net-(D31-PadC)") (class "Default")
      (node (ref "D31") (pin "C") (pinfunction "C_C") (pintype "passive"))
      (node (ref "D32") (pin "A") (pinfunction "A_A") (pintype "passive"))
    )
    (net (code "32") (name "Net-(D32-PadC)") (class "Default")
      (node (ref "D32") (pin "C") (pinfunction "C_C") (pintype "passive"))
      (node (ref "D33") (pin "A") (pinfunction "A_A") (pintype "passive"))
    )
    (net (code "33") (name "Net-(D33-PadC)") (class "Default")
      (node (ref "D33") (pin "C") (pinfunction "C_C") (pintype "passive"))
      (node (ref "D34") (pin "A") (pinfunction "A_A") (pintype "passive"))
    )
    (net (code "34") (name "Net-(D34-PadC)") (class "Default")
      (node (ref "D34") (pin "C") (pinfunction "C_C") (pintype "passive"))
      (node (ref "D35") (pin "A") (pinfunction "A_A") (pintype "passive"))
    )
    (net (code "35") (name "Net-(D35-PadC)") (class "Default")
      (node (ref "D35") (pin "C") (pinfunction "C_C") (pintype "passive"))
      (node (ref "D36") (pin "A") (pinfunction "A_A") (pintype "passive"))
    )
    (net (code "36") (name "Net-(D36-PadC)") (class "Default")
      (node (ref "D36") (pin "C") (pinfunction "C_C") (pintype "passive"))
      (node (ref "D37") (pin "A") (pinfunction "A_A") (pintype "passive"))
    )
    (net (code "37") (name "Net-(D37-PadC)") (class "Default")
      (node (ref "D37") (pin "C") (pinfunction "C_C") (pintype "passive"))
      (node (ref "D38") (pin "A") (pinfunction "A_A") (pintype "passive"))
    )
    (net (code "38") (name "Net-(D38-PadC)") (class "Default")
      (node (ref "D38") (pin "C") (pinfunction "C_C") (pintype "passive"))
      (node (ref "D39") (pin "A") (pinfunction "A_A") (pintype "passive"))
    )
    (net (code "39") (name "Net-(D39-PadC)") (class "Default")
      (node (ref "D39") (pin "C") (pinfunction "C_C") (pintype "passive"))
      (node (ref "D40") (pin "A") (pinfunction "A_A") (pintype "passive"))
    )
    (net (code "40") (name "Net-(D40-PadC)") (class "Default")
      (node (ref "D40") (pin "C") (pinfunction "C_C") (pintype "passive"))
      (node (ref "D41") (pin "A") (pinfunction "A_A") (pintype "passive"))
    )
    (net (code "41") (name "Net-(D41-PadC)") (class "Default")
      (node (ref "D41") (pin "C") (pinfunction "C_C") (pintype "passive"))
      (node (ref "D42") (pin "A") (pinfunction "A_A") (pintype "passive"))
    )
    (net (code "42") (name "Net-(D43-PadC)") (class "Default")
      (node (ref "D43") (pin "C") (pinfunction "C_C") (pintype "passive"))
      (node (ref "D44") (pin "A") (pinfunction "A_A") (pintype "passive"))
    )
    (net (code "43") (name "Net-(D44-PadC)") (class "Default")
      (node (ref "D44") (pin "C") (pinfunction "C_C") (pintype "passive"))
      (node (ref "D45") (pin "A") (pinfunction "A_A") (pintype "passive"))
    )
    (net (code "44") (name "Net-(D45-PadC)") (class "Default")
      (node (ref "D45") (pin "C") (pinfunction "C_C") (pintype "passive"))
      (node (ref "D46") (pin "A") (pinfunction "A_A") (pintype "passive"))
    )
    (net (code "45") (name "Net-(D46-PadC)") (class "Default")
      (node (ref "D46") (pin "C") (pinfunction "C_C") (pintype "passive"))
      (node (ref "D47") (pin "A") (pinfunction "A_A") (pintype "passive"))
    )
    (net (code "46") (name "Net-(D47-PadC)") (class "Default")
      (node (ref "D47") (pin "C") (pinfunction "C_C") (pintype "passive"))
      (node (ref "D48") (pin "A") (pinfunction "A_A") (pintype "passive"))
    )
    (net (code "47") (name "Net-(D48-PadC)") (class "Default")
      (node (ref "D48") (pin "C") (pinfunction "C_C") (pintype "passive"))
      (node (ref "D49") (pin "A") (pinfunction "A_A") (pintype "passive"))
    )
    (net (code "48") (name "Net-(D49-PadC)") (class "Default")
      (node (ref "D49") (pin "C") (pinfunction "C_C") (pintype "passive"))
      (node (ref "D50") (pin "A") (pinfunction "A_A") (pintype "passive"))
    )
    (net (code "49") (name "Net-(D50-PadC)") (class "Default")
      (node (ref "D50") (pin "C") (pinfunction "C_C") (pintype "passive"))
      (node (ref "D51") (pin "A") (pinfunction "A_A") (pintype "passive"))
    )
    (net (code "50") (name "Net-(D51-PadC)") (class "Default")
      (node (ref "D51") (pin "C") (pinfunction "C_C") (pintype "passive"))
      (node (ref "D52") (pin "A") (pinfunction "A_A") (pintype "passive"))
    )
    (net (code "51") (name "Net-(D52-PadC)") (class "Default")
      (node (ref "D52") (pin "C") (pinfunction "C_C") (pintype "passive"))
      (node (ref "D53") (pin "A") (pinfunction "A_A") (pintype "passive"))
    )
    (net (code "52") (name "Net-(D53-PadC)") (class "Default")
      (node (ref "D53") (pin "C") (pinfunction "C_C") (pintype "passive"))
      (node (ref "D54") (pin "A") (pinfunction "A_A") (pintype "passive"))
    )
    (net (code "53") (name "Net-(D54-PadC)") (class "Default")
      (node (ref "D54") (pin "C") (pinfunction "C_C") (pintype "passive"))
      (node (ref "D55") (pin "A") (pinfunction "A_A") (pintype "passive"))
    )
    (net (code "54") (name "Net-(D55-PadC)") (class "Default")
      (node (ref "D55") (pin "C") (pinfunction "C_C") (pintype "passive"))
      (node (ref "D56") (pin "A") (pinfunction "A_A") (pintype "passive"))
    )
    (net (code "55") (name "Net-(D56-PadC)") (class "Default")
      (node (ref "D56") (pin "C") (pinfunction "C_C") (pintype "passive"))
      (node (ref "D57") (pin "A") (pinfunction "A_A") (pintype "passive"))
    )
    (net (code "56") (name "Net-(D57-PadC)") (class "Default")
      (node (ref "D57") (pin "C") (pinfunction "C_C") (pintype "passive"))
      (node (ref "D58") (pin "A") (pinfunction "A_A") (pintype "passive"))
    )
    (net (code "57") (name "Net-(D58-PadC)") (class "Default")
      (node (ref "D58") (pin "C") (pinfunction "C_C") (pintype "passive"))
      (node (ref "D59") (pin "A") (pinfunction "A_A") (pintype "passive"))
    )
    (net (code "58") (name "Net-(D59-PadC)") (class "Default")
      (node (ref "D59") (pin "C") (pinfunction "C_C") (pintype "passive"))
      (node (ref "D60") (pin "A") (pinfunction "A_A") (pintype "passive"))
    )
    (net (code "59") (name "Net-(D60-PadC)") (class "Default")
      (node (ref "D60") (pin "C") (pinfunction "C_C") (pintype "passive"))
      (node (ref "D61") (pin "A") (pinfunction "A_A") (pintype "passive"))
    )
    (net (code "60") (name "Net-(D61-PadC)") (class "Default")
      (node (ref "D61") (pin "C") (pinfunction "C_C") (pintype "passive"))
      (node (ref "D62") (pin "A") (pinfunction "A_A") (pintype "passive"))
    )
    (net (code "61") (name "Net-(D62-PadC)") (class "Default")
      (node (ref "D62") (pin "C") (pinfunction "C_C") (pintype "passive"))
      (node (ref "D63") (pin "A") (pinfunction "A_A") (pintype "passive"))
    )
    (net (code "62") (name "Net-(D64-PadC)") (class "Default")
      (node (ref "D64") (pin "C") (pinfunction "C_C") (pintype "passive"))
      (node (ref "D65") (pin "A") (pinfunction "A_A") (pintype "passive"))
    )
    (net (code "63") (name "Net-(D65-PadC)") (class "Default")
      (node (ref "D65") (pin "C") (pinfunction "C_C") (pintype "passive"))
      (node (ref "D66") (pin "A") (pinfunction "A_A") (pintype "passive"))
    )
    (net (code "64") (name "Net-(D66-PadC)") (class "Default")
      (node (ref "D66") (pin "C") (pinfunction "C_C") (pintype "passive"))
      (node (ref "D67") (pin "A") (pinfunction "A_A") (pintype "passive"))
    )
    (net (code "65") (name "Net-(D67-PadC)") (class "Default")
      (node (ref "D67") (pin "C") (pinfunction "C_C") (pintype "passive"))
      (node (ref "D68") (pin "A") (pinfunction "A_A") (pintype "passive"))
    )
    (net (code "66") (name "Net-(D68-PadC)") (class "Default")
      (node (ref "D68") (pin "C") (pinfunction "C_C") (pintype "passive"))
      (node (ref "D69") (pin "A") (pinfunction "A_A") (pintype "passive"))
    )
    (net (code "67") (name "Net-(D69-PadC)") (class "Default")
      (node (ref "D69") (pin "C") (pinfunction "C_C") (pintype "passive"))
      (node (ref "D70") (pin "A") (pinfunction "A_A") (pintype "passive"))
    )
    (net (code "68") (name "Net-(D70-PadC)") (class "Default")
      (node (ref "D70") (pin "C") (pinfunction "C_C") (pintype "passive"))
      (node (ref "D71") (pin "A") (pinfunction "A_A") (pintype "passive"))
    )
    (net (code "69") (name "Net-(D71-PadC)") (class "Default")
      (node (ref "D71") (pin "C") (pinfunction "C_C") (pintype "passive"))
      (node (ref "D72") (pin "A") (pinfunction "A_A") (pintype "passive"))
    )
    (net (code "70") (name "Net-(D72-PadC)") (class "Default")
      (node (ref "D72") (pin "C") (pinfunction "C_C") (pintype "passive"))
      (node (ref "D73") (pin "A") (pinfunction "A_A") (pintype "passive"))
    )
    (net (code "71") (name "Net-(D73-PadC)") (class "Default")
      (node (ref "D73") (pin "C") (pinfunction "C_C") (pintype "passive"))
      (node (ref "D74") (pin "A") (pinfunction "A_A") (pintype "passive"))
    )
    (net (code "72") (name "Net-(D74-PadC)") (class "Default")
      (node (ref "D74") (pin "C") (pinfunction "C_C") (pintype "passive"))
      (node (ref "D75") (pin "A") (pinfunction "A_A") (pintype "passive"))
    )
    (net (code "73") (name "Net-(D75-PadC)") (class "Default")
      (node (ref "D75") (pin "C") (pinfunction "C_C") (pintype "passive"))
      (node (ref "D76") (pin "A") (pinfunction "A_A") (pintype "passive"))
    )
    (net (code "74") (name "Net-(D76-PadC)") (class "Default")
      (node (ref "D76") (pin "C") (pinfunction "C_C") (pintype "passive"))
      (node (ref "D77") (pin "A") (pinfunction "A_A") (pintype "passive"))
    )
    (net (code "75") (name "Net-(D77-PadC)") (class "Default")
      (node (ref "D77") (pin "C") (pinfunction "C_C") (pintype "passive"))
      (node (ref "D78") (pin "A") (pinfunction "A_A") (pintype "passive"))
    )
    (net (code "76") (name "Net-(D78-PadC)") (class "Default")
      (node (ref "D78") (pin "C") (pinfunction "C_C") (pintype "passive"))
      (node (ref "D79") (pin "A") (pinfunction "A_A") (pintype "passive"))
    )
    (net (code "77") (name "Net-(D79-PadC)") (class "Default")
      (node (ref "D79") (pin "C") (pinfunction "C_C") (pintype "passive"))
      (node (ref "D80") (pin "A") (pinfunction "A_A") (pintype "passive"))
    )
    (net (code "78") (name "Net-(D80-PadC)") (class "Default")
      (node (ref "D80") (pin "C") (pinfunction "C_C") (pintype "passive"))
      (node (ref "D81") (pin "A") (pinfunction "A_A") (pintype "passive"))
    )
    (net (code "79") (name "Net-(D81-PadC)") (class "Default")
      (node (ref "D81") (pin "C") (pinfunction "C_C") (pintype "passive"))
      (node (ref "D82") (pin "A") (pinfunction "A_A") (pintype "passive"))
    )
    (net (code "80") (name "Net-(D82-PadC)") (class "Default")
      (node (ref "D82") (pin "C") (pinfunction "C_C") (pintype "passive"))
      (node (ref "D83") (pin "A") (pinfunction "A_A") (pintype "passive"))
    )
    (net (code "81") (name "Net-(D83-PadC)") (class "Default")
      (node (ref "D83") (pin "C") (pinfunction "C_C") (pintype "passive"))
      (node (ref "D84") (pin "A") (pinfunction "A_A") (pintype "passive"))
    )
    (net (code "82") (name "Net-(D85-PadC)") (class "Default")
      (node (ref "D85") (pin "C") (pinfunction "C_C") (pintype "passive"))
      (node (ref "D86") (pin "A") (pinfunction "A_A") (pintype "passive"))
    )
    (net (code "83") (name "Net-(D86-PadC)") (class "Default")
      (node (ref "D86") (pin "C") (pinfunction "C_C") (pintype "passive"))
      (node (ref "D87") (pin "A") (pinfunction "A_A") (pintype "passive"))
    )
    (net (code "84") (name "Net-(D87-PadC)") (class "Default")
      (node (ref "D87") (pin "C") (pinfunction "C_C") (pintype "passive"))
      (node (ref "D88") (pin "A") (pinfunction "A_A") (pintype "passive"))
    )
    (net (code "85") (name "Net-(D88-PadC)") (class "Default")
      (node (ref "D88") (pin "C") (pinfunction "C_C") (pintype "passive"))
      (node (ref "D89") (pin "A") (pinfunction "A_A") (pintype "passive"))
    )
    (net (code "86") (name "Net-(D89-PadC)") (class "Default")
      (node (ref "D89") (pin "C") (pinfunction "C_C") (pintype "passive"))
      (node (ref "D90") (pin "A") (pinfunction "A_A") (pintype "passive"))
    )
    (net (code "87") (name "Net-(D90-PadC)") (class "Default")
      (node (ref "D90") (pin "C") (pinfunction "C_C") (pintype "passive"))
      (node (ref "D91") (pin "A") (pinfunction "A_A") (pintype "passive"))
    )
    (net (code "88") (name "Net-(D91-PadC)") (class "Default")
      (node (ref "D91") (pin "C") (pinfunction "C_C") (pintype "passive"))
      (node (ref "D92") (pin "A") (pinfunction "A_A") (pintype "passive"))
    )
    (net (code "89") (name "Net-(D92-PadC)") (class "Default")
      (node (ref "D92") (pin "C") (pinfunction "C_C") (pintype "passive"))
      (node (ref "D93") (pin "A") (pinfunction "A_A") (pintype "passive"))
    )
    (net (code "90") (name "Net-(D93-PadC)") (class "Default")
      (node (ref "D93") (pin "C") (pinfunction "C_C") (pintype "passive"))
      (node (ref "D94") (pin "A") (pinfunction "A_A") (pintype "passive"))
    )
    (net (code "91") (name "Net-(D94-PadC)") (class "Default")
      (node (ref "D94") (pin "C") (pinfunction "C_C") (pintype "passive"))
      (node (ref "D95") (pin "A") (pinfunction "A_A") (pintype "passive"))
    )
    (net (code "92") (name "Net-(D95-PadC)") (class "Default")
      (node (ref "D95") (pin "C") (pinfunction "C_C") (pintype "passive"))
      (node (ref "D96") (pin "A") (pinfunction "A_A") (pintype "passive"))
    )
    (net (code "93") (name "Net-(D96-PadC)") (class "Default")
      (node (ref "D96") (pin "C") (pinfunction "C_C") (pintype "passive"))
      (node (ref "D97") (pin "A") (pinfunction "A_A") (pintype "passive"))
    )
    (net (code "94") (name "Net-(D97-PadC)") (class "Default")
      (node (ref "D97") (pin "C") (pinfunction "C_C") (pintype "passive"))
      (node (ref "D98") (pin "A") (pinfunction "A_A") (pintype "passive"))
    )
    (net (code "95") (name "Net-(D98-PadC)") (class "Default")
      (node (ref "D98") (pin "C") (pinfunction "C_C") (pintype "passive"))
      (node (ref "D99") (pin "A") (pinfunction "A_A") (pintype "passive"))
    )
    (net (code "96") (name "Net-(D100-PadA)") (class "Default")
      (node (ref "D100") (pin "A") (pinfunction "A_A") (pintype "passive"))
      (node (ref "D99") (pin "C") (pinfunction "C_C") (pintype "passive"))
    )
    (net (code "97") (name "Net-(D100-PadC)") (class "Default")
      (node (ref "D100") (pin "C") (pinfunction "C_C") (pintype "passive"))
      (node (ref "D101") (pin "A") (pinfunction "A_A") (pintype "passive"))
    )
    (net (code "98") (name "Net-(D101-PadC)") (class "Default")
      (node (ref "D101") (pin "C") (pinfunction "C_C") (pintype "passive"))
      (node (ref "D102") (pin "A") (pinfunction "A_A") (pintype "passive"))
    )
    (net (code "99") (name "Net-(D102-PadC)") (class "Default")
      (node (ref "D102") (pin "C") (pinfunction "C_C") (pintype "passive"))
      (node (ref "D103") (pin "A") (pinfunction "A_A") (pintype "passive"))
    )
    (net (code "100") (name "Net-(D103-PadC)") (class "Default")
      (node (ref "D103") (pin "C") (pinfunction "C_C") (pintype "passive"))
      (node (ref "D104") (pin "A") (pinfunction "A_A") (pintype "passive"))
    )
    (net (code "101") (name "Net-(D104-PadC)") (class "Default")
      (node (ref "D104") (pin "C") (pinfunction "C_C") (pintype "passive"))
      (node (ref "D105") (pin "A") (pinfunction "A_A") (pintype "passive"))
    )
    (net (code "102") (name "Net-(D106-PadC)") (class "Default")
      (node (ref "D106") (pin "C") (pinfunction "C_C") (pintype "passive"))
      (node (ref "D107") (pin "A") (pinfunction "A_A") (pintype "passive"))
    )
    (net (code "103") (name "Net-(D107-PadC)") (class "Default")
      (node (ref "D107") (pin "C") (pinfunction "C_C") (pintype "passive"))
      (node (ref "D108") (pin "A") (pinfunction "A_A") (pintype "passive"))
    )
    (net (code "104") (name "Net-(D108-PadC)") (class "Default")
      (node (ref "D108") (pin "C") (pinfunction "C_C") (pintype "passive"))
      (node (ref "D109") (pin "A") (pinfunction "A_A") (pintype "passive"))
    )
    (net (code "105") (name "Net-(D109-PadC)") (class "Default")
      (node (ref "D109") (pin "C") (pinfunction "C_C") (pintype "passive"))
      (node (ref "D110") (pin "A") (pinfunction "A_A") (pintype "passive"))
    )
    (net (code "106") (name "Net-(D110-PadC)") (class "Default")
      (node (ref "D110") (pin "C") (pinfunction "C_C") (pintype "passive"))
      (node (ref "D111") (pin "A") (pinfunction "A_A") (pintype "passive"))
    )
    (net (code "107") (name "Net-(D111-PadC)") (class "Default")
      (node (ref "D111") (pin "C") (pinfunction "C_C") (pintype "passive"))
      (node (ref "D112") (pin "A") (pinfunction "A_A") (pintype "passive"))
    )
    (net (code "108") (name "Net-(D112-PadC)") (class "Default")
      (node (ref "D112") (pin "C") (pinfunction "C_C") (pintype "passive"))
      (node (ref "D113") (pin "A") (pinfunction "A_A") (pintype "passive"))
    )
    (net (code "109") (name "Net-(D113-PadC)") (class "Default")
      (node (ref "D113") (pin "C") (pinfunction "C_C") (pintype "passive"))
      (node (ref "D114") (pin "A") (pinfunction "A_A") (pintype "passive"))
    )
    (net (code "110") (name "Net-(D114-PadC)") (class "Default")
      (node (ref "D114") (pin "C") (pinfunction "C_C") (pintype "passive"))
      (node (ref "D115") (pin "A") (pinfunction "A_A") (pintype "passive"))
    )
    (net (code "111") (name "Net-(D115-PadC)") (class "Default")
      (node (ref "D115") (pin "C") (pinfunction "C_C") (pintype "passive"))
      (node (ref "D116") (pin "A") (pinfunction "A_A") (pintype "passive"))
    )
    (net (code "112") (name "Net-(D116-PadC)") (class "Default")
      (node (ref "D116") (pin "C") (pinfunction "C_C") (pintype "passive"))
      (node (ref "D117") (pin "A") (pinfunction "A_A") (pintype "passive"))
    )
    (net (code "113") (name "Net-(D117-PadC)") (class "Default")
      (node (ref "D117") (pin "C") (pinfunction "C_C") (pintype "passive"))
      (node (ref "D118") (pin "A") (pinfunction "A_A") (pintype "passive"))
    )
    (net (code "114") (name "Net-(D118-PadC)") (class "Default")
      (node (ref "D118") (pin "C") (pinfunction "C_C") (pintype "passive"))
      (node (ref "D119") (pin "A") (pinfunction "A_A") (pintype "passive"))
    )
    (net (code "115") (name "Net-(D119-PadC)") (class "Default")
      (node (ref "D119") (pin "C") (pinfunction "C_C") (pintype "passive"))
      (node (ref "D120") (pin "A") (pinfunction "A_A") (pintype "passive"))
    )
    (net (code "116") (name "Net-(D120-PadC)") (class "Default")
      (node (ref "D120") (pin "C") (pinfunction "C_C") (pintype "passive"))
      (node (ref "D121") (pin "A") (pinfunction "A_A") (pintype "passive"))
    )
    (net (code "117") (name "Net-(D121-PadC)") (class "Default")
      (node (ref "D121") (pin "C") (pinfunction "C_C") (pintype "passive"))
      (node (ref "D122") (pin "A") (pinfunction "A_A") (pintype "passive"))
    )
    (net (code "118") (name "Net-(D122-PadC)") (class "Default")
      (node (ref "D122") (pin "C") (pinfunction "C_C") (pintype "passive"))
      (node (ref "D123") (pin "A") (pinfunction "A_A") (pintype "passive"))
    )
    (net (code "119") (name "Net-(D123-PadC)") (class "Default")
      (node (ref "D123") (pin "C") (pinfunction "C_C") (pintype "passive"))
      (node (ref "D124") (pin "A") (pinfunction "A_A") (pintype "passive"))
    )
    (net (code "120") (name "Net-(D124-PadC)") (class "Default")
      (node (ref "D124") (pin "C") (pinfunction "C_C") (pintype "passive"))
      (node (ref "D125") (pin "A") (pinfunction "A_A") (pintype "passive"))
    )
    (net (code "121") (name "Net-(D125-PadC)") (class "Default")
      (node (ref "D125") (pin "C") (pinfunction "C_C") (pintype "passive"))
      (node (ref "D126") (pin "A") (pinfunction "A_A") (pintype "passive"))
    )
    (net (code "122") (name "VCC") (class "Default")
      (node (ref "D1") (pin "A") (pinfunction "A_A") (pintype "passive"))
      (node (ref "D106") (pin "A") (pinfunction "A_A") (pintype "passive"))
      (node (ref "D22") (pin "A") (pinfunction "A_A") (pintype "passive"))
      (node (ref "D43") (pin "A") (pinfunction "A_A") (pintype "passive"))
      (node (ref "D64") (pin "A") (pinfunction "A_A") (pintype "passive"))
      (node (ref "D85") (pin "A") (pinfunction "A_A") (pintype "passive"))
      (node (ref "P1") (pin "VCC") (pinfunction "1_VCC") (pintype "passive"))
    )
  )
)
